# TLV76701.net
KiCad netlist of a schematic drawn in Altium Designer
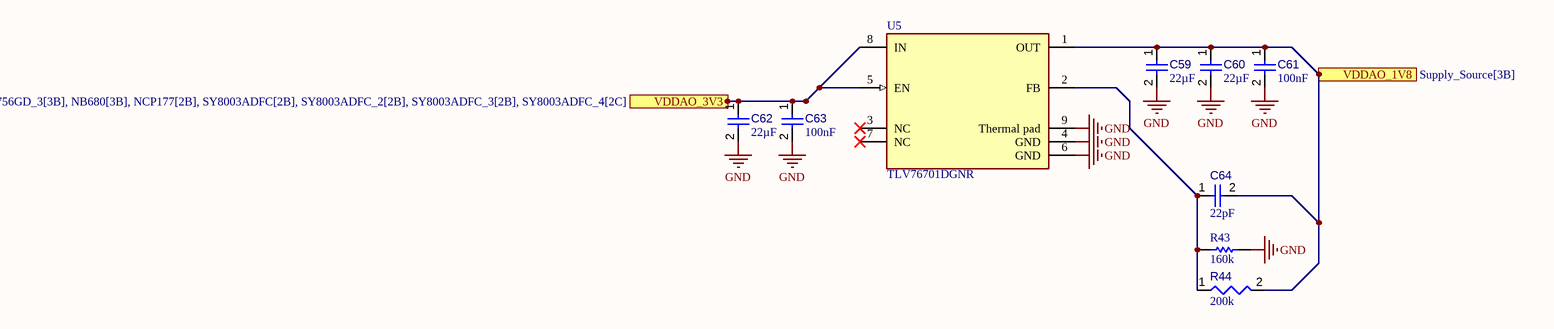
[diagram p0: TLV76701.SchDoc]

(export (version "E")
  (design (tool "Eeschema 10.0.6"))
  (components
    (comp (ref "C59")
      (value "22µF")
      (footprint "CAPC0805(2012)145_L")
      (description "Chip Capacitor, 22µF +/-40%, 16V, 0805, Thickness 1.45 mm")
      (fields (field (name "TOLERANCE") "5%") (field (name "Comment") "Capacitor 22µF +/-40% 16V 0805"))
      (libsource (lib "MIGUEL ANGEL ALVAREZ GUZMAN") (part "CAP-NP-2"))
    )
    (comp (ref "C60")
      (value "22µF")
      (footprint "CAPC0805(2012)145_L")
      (description "Chip Capacitor, 22µF +/-40%, 16V, 0805, Thickness 1.45 mm")
      (fields (field (name "TOLERANCE") "5%") (field (name "Comment") "Capacitor 22µF +/-40% 16V 0805"))
      (libsource (lib "MIGUEL ANGEL ALVAREZ GUZMAN") (part "CAP-NP-2"))
    )
    (comp (ref "C61")
      (value "100nF")
      (footprint "CAPC0402(1005)60_L")
      (description "Chip Capacitor, 100nF +/-20%, 25V, 0402, Thickness 0.6 mm")
      (fields (field (name "TOLERANCE") "10%") (field (name "Comment") "Capacitor 100nF +/-20% 25V 0402"))
      (libsource (lib "MIGUEL ANGEL ALVAREZ GUZMAN") (part "CAP-NP-2"))
    )
    (comp (ref "C62")
      (value "22µF")
      (footprint "CAPC0805(2012)145_L")
      (description "Chip Capacitor, 22µF +/-40%, 16V, 0805, Thickness 1.45 mm")
      (fields (field (name "TOLERANCE") "5%") (field (name "Comment") "Capacitor 22µF +/-40% 16V 0805"))
      (libsource (lib "MIGUEL ANGEL ALVAREZ GUZMAN") (part "CAP-NP-2"))
    )
    (comp (ref "C63")
      (value "100nF")
      (footprint "CAPC0402(1005)60_L")
      (description "Chip Capacitor, 100nF +/-20%, 25V, 0402, Thickness 0.6 mm")
      (fields (field (name "TOLERANCE") "10%") (field (name "Comment") "Capacitor 100nF +/-20% 25V 0402"))
      (libsource (lib "MIGUEL ANGEL ALVAREZ GUZMAN") (part "CAP-NP-2"))
    )
    (comp (ref "C64")
      (value "22pF")
      (footprint "CAPC0402(1005)60_L")
      (description "Chip Capacitor, 22pF +/-10%, 50V, 0402, Thickness 0.6 mm")
      (fields (field (name "TOLERANCE") "10%") (field (name "Comment") "Capacitor 22pF +/-10% 50V 0402"))
      (libsource (lib "MIGUEL ANGEL ALVAREZ GUZMAN") (part "CAP-NP-2"))
    )
    (comp (ref "R43")
      (value "160k")
      (footprint "RESC0603X28X15ML05T05")
      (description "CRCW Series 0201 160 kOhm ±1% 0.05 W ±200 ppm/K Thick Film Chip Resistor")
      (fields (field (name "TOLERANCE") "1%") (field (name "Comment") "CRCW0201160KFNED"))
      (libsource (lib "MIGUEL ANGEL ALVAREZ GUZMAN") (part "RES"))
    )
    (comp (ref "R44")
      (value "200k")
      (footprint "RESC0402(1005)_L")
      (description "Chip Resistor, 200 kOhms, +/-1 %, 63 mW, -55 to 155 degC, 0402")
      (fields (field (name "POWER") "63mW") (field (name "TOLERANCE") "1%"))
      (libsource (lib "MIGUEL ANGEL ALVAREZ GUZMAN") (part "RES-2"))
    )
    (comp (ref "U5")
      (value "TLV76701DGNR")
      (footprint "FP-DGN0008G-MFG")
      (libsource (lib "Altium Content Vault") (part "4137fefd6f2351a27154aa09bf60b26"))
    )
  )
  (nets
    (net (code "1") (name "/VDDAO_1V8") (class "Default")
      (node (ref "C59") (pin "1") (pinfunction "1_1") (pintype "passive"))
      (node (ref "C60") (pin "1") (pinfunction "1_1") (pintype "passive"))
      (node (ref "C61") (pin "1") (pinfunction "1_1") (pintype "passive"))
      (node (ref "C64") (pin "2") (pinfunction "2_2") (pintype "passive"))
      (node (ref "R44") (pin "2") (pinfunction "2_2") (pintype "passive"))
      (node (ref "U5") (pin "1") (pinfunction "OUT_1") (pintype "passive"))
    )
    (net (code "2") (name "/VDDAO_3V3") (class "Default")
      (node (ref "C62") (pin "1") (pinfunction "1_1") (pintype "passive"))
      (node (ref "C63") (pin "1") (pinfunction "1_1") (pintype "passive"))
      (node (ref "U5") (pin "5") (pinfunction "EN_5") (pintype "input"))
      (node (ref "U5") (pin "8") (pinfunction "IN_8") (pintype "power_in"))
    )
    (net (code "3") (name "GND") (class "Default")
      (node (ref "C59") (pin "2") (pinfunction "2_2") (pintype "passive"))
      (node (ref "C60") (pin "2") (pinfunction "2_2") (pintype "passive"))
      (node (ref "C61") (pin "2") (pinfunction "2_2") (pintype "passive"))
      (node (ref "C62") (pin "2") (pinfunction "2_2") (pintype "passive"))
      (node (ref "C63") (pin "2") (pinfunction "2_2") (pintype "passive"))
      (node (ref "R43") (pin "2") (pinfunction "2_2") (pintype "passive"))
      (node (ref "U5") (pin "4") (pinfunction "GND_4") (pintype "power_in"))
      (node (ref "U5") (pin "6") (pinfunction "GND_6") (pintype "power_in"))
      (node (ref "U5") (pin "9") (pinfunction "Thermal_pad_9") (pintype "power_in"))
    )
    (net (code "4") (name "Net-(U5-FB)") (class "Default")
      (node (ref "C64") (pin "1") (pinfunction "1_1") (pintype "passive"))
      (node (ref "R43") (pin "1") (pinfunction "1_1") (pintype "passive"))
      (node (ref "R44") (pin "1") (pinfunction "1_1") (pintype "passive"))
      (node (ref "U5") (pin "2") (pinfunction "FB_2") (pintype "passive"))
    )
    (net (code "5") (name "unconnected-(U5-NC-Pad3)") (class "Default")
      (node (ref "U5") (pin "3") (pinfunction "NC_3") (pintype "passive+no_connect"))
    )
    (net (code "6") (name "unconnected-(U5-NC-Pad7)") (class "Default")
      (node (ref "U5") (pin "7") (pinfunction "NC_7") (pintype "passive+no_connect"))
    )
  )
)
